# BluetoothModulePCBv1.net
KiCad netlist of a schematic drawn in EAGLE
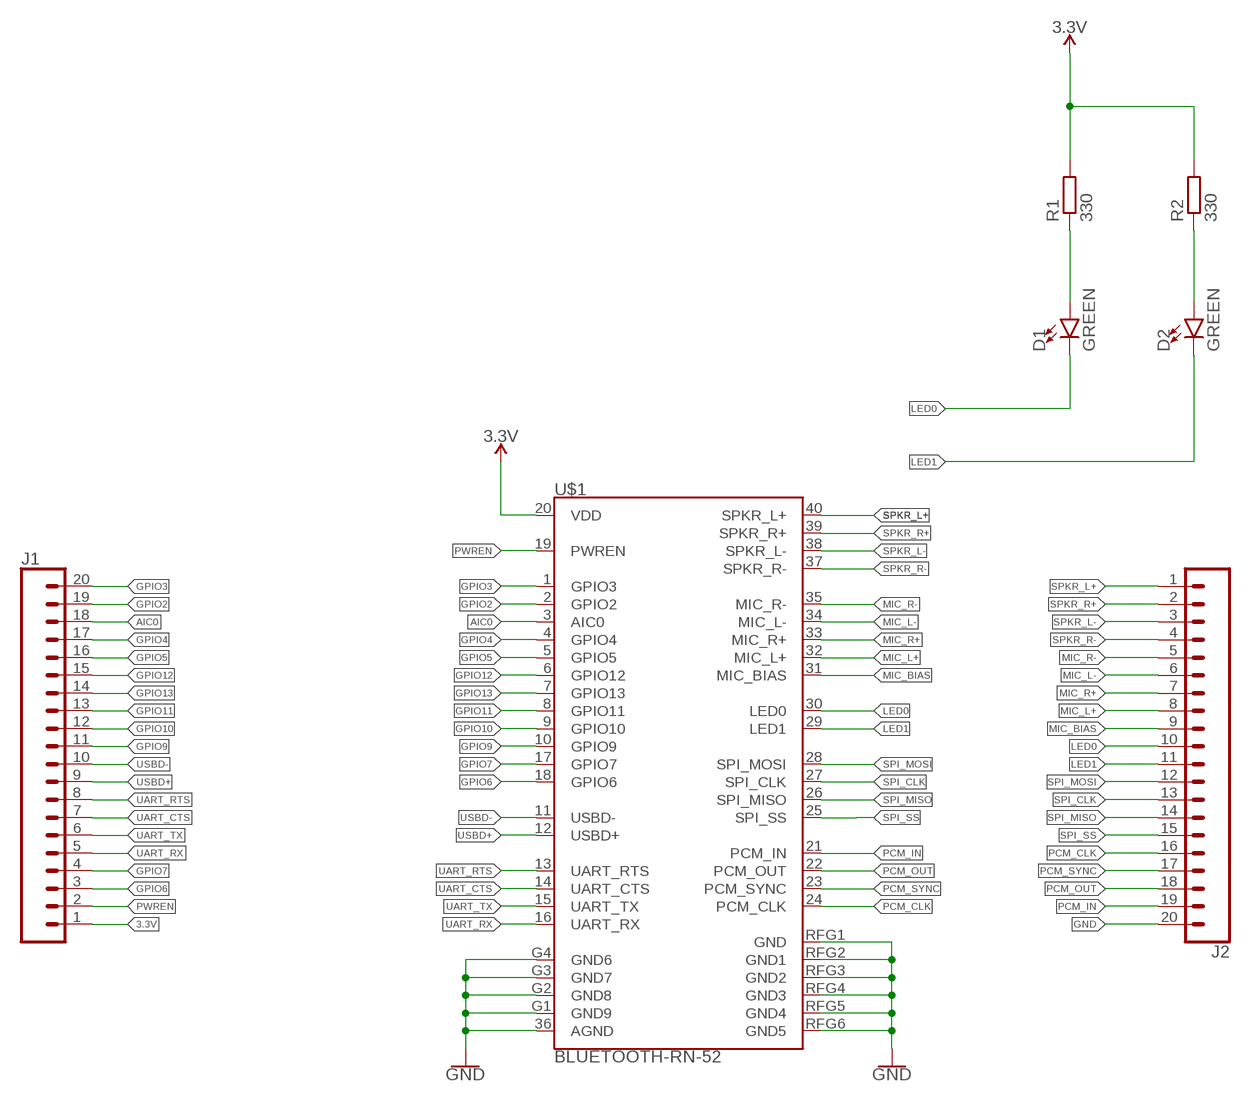
[diagram p0: schematic, sheet 1]

(export (version "E")
  (design (tool "Eeschema 10.0.6"))
  (components
    (comp (ref "D1")
      (value "GREEN")
      (footprint "eagle-import:LED_3MM")
      (libsource (lib "eagle-import") (part "LED3MM"))
    )
    (comp (ref "D2")
      (value "GREEN")
      (footprint "eagle-import:LED_3MM")
      (libsource (lib "eagle-import") (part "LED3MM"))
    )
    (comp (ref "J1")
      (value "CONN_20")
      (footprint "eagle-import:1X20")
      (libsource (lib "eagle-import") (part "CONN_20"))
    )
    (comp (ref "J2")
      (value "CONN_20")
      (footprint "eagle-import:1X20")
      (libsource (lib "eagle-import") (part "CONN_20"))
    )
    (comp (ref "R1")
      (value "330")
      (footprint "eagle-import:0204_7")
      (libsource (lib "eagle-import") (part "R-EU_0204/7"))
    )
    (comp (ref "R2")
      (value "330")
      (footprint "eagle-import:0204_7")
      (libsource (lib "eagle-import") (part "R-EU_0204/7"))
    )
    (comp (ref "U$1")
      (value "BLUETOOTH-RN-52")
      (footprint "eagle-import:RN-52")
      (libsource (lib "eagle-import") (part "BLUETOOTH-RN-52"))
    )
  )
  (nets
    (net (code "1") (name "3.3V") (class "Default")
      (node (ref "J1") (pin "1") (pinfunction "1_1") (pintype "passive"))
      (node (ref "R1") (pin "2") (pinfunction "2_2") (pintype "passive"))
      (node (ref "R2") (pin "2") (pinfunction "2_2") (pintype "passive"))
      (node (ref "U$1") (pin "20") (pinfunction "VDD_20") (pintype "bidirectional"))
    )
    (net (code "2") (name "AIC0") (class "Default")
      (node (ref "J1") (pin "18") (pinfunction "18_18") (pintype "passive"))
      (node (ref "U$1") (pin "3") (pinfunction "AIC0_3") (pintype "bidirectional"))
    )
    (net (code "3") (name "GND") (class "Default")
      (node (ref "J2") (pin "20") (pinfunction "20_20") (pintype "passive"))
      (node (ref "U$1") (pin "36") (pinfunction "AGND_36") (pintype "bidirectional"))
      (node (ref "U$1") (pin "G1") (pinfunction "GND9_G1") (pintype "bidirectional"))
      (node (ref "U$1") (pin "G2") (pinfunction "GND8_G2") (pintype "bidirectional"))
      (node (ref "U$1") (pin "G3") (pinfunction "GND7_G3") (pintype "bidirectional"))
      (node (ref "U$1") (pin "G4") (pinfunction "GND6_G4") (pintype "bidirectional"))
      (node (ref "U$1") (pin "RFG1") (pinfunction "GND_RFG1") (pintype "bidirectional"))
      (node (ref "U$1") (pin "RFG2") (pinfunction "GND1_RFG2") (pintype "bidirectional"))
      (node (ref "U$1") (pin "RFG3") (pinfunction "GND2_RFG3") (pintype "bidirectional"))
      (node (ref "U$1") (pin "RFG4") (pinfunction "GND3_RFG4") (pintype "bidirectional"))
      (node (ref "U$1") (pin "RFG5") (pinfunction "GND4_RFG5") (pintype "bidirectional"))
      (node (ref "U$1") (pin "RFG6") (pinfunction "GND5_RFG6") (pintype "bidirectional"))
    )
    (net (code "4") (name "GPIO2") (class "Default")
      (node (ref "J1") (pin "19") (pinfunction "19_19") (pintype "passive"))
      (node (ref "U$1") (pin "2") (pinfunction "GPIO2_2") (pintype "bidirectional"))
    )
    (net (code "5") (name "GPIO3") (class "Default")
      (node (ref "J1") (pin "20") (pinfunction "20_20") (pintype "passive"))
      (node (ref "U$1") (pin "1") (pinfunction "GPIO3_1") (pintype "bidirectional"))
    )
    (net (code "6") (name "GPIO4") (class "Default")
      (node (ref "J1") (pin "17") (pinfunction "17_17") (pintype "passive"))
      (node (ref "U$1") (pin "4") (pinfunction "GPIO4_4") (pintype "bidirectional"))
    )
    (net (code "7") (name "GPIO5") (class "Default")
      (node (ref "J1") (pin "16") (pinfunction "16_16") (pintype "passive"))
      (node (ref "U$1") (pin "5") (pinfunction "GPIO5_5") (pintype "bidirectional"))
    )
    (net (code "8") (name "GPIO6") (class "Default")
      (node (ref "J1") (pin "3") (pinfunction "3_3") (pintype "passive"))
      (node (ref "U$1") (pin "18") (pinfunction "GPIO6_18") (pintype "bidirectional"))
    )
    (net (code "9") (name "GPIO7") (class "Default")
      (node (ref "J1") (pin "4") (pinfunction "4_4") (pintype "passive"))
      (node (ref "U$1") (pin "17") (pinfunction "GPIO7_17") (pintype "bidirectional"))
    )
    (net (code "10") (name "GPIO9") (class "Default")
      (node (ref "J1") (pin "11") (pinfunction "11_11") (pintype "passive"))
      (node (ref "U$1") (pin "10") (pinfunction "GPIO9_10") (pintype "bidirectional"))
    )
    (net (code "11") (name "GPIO10") (class "Default")
      (node (ref "J1") (pin "12") (pinfunction "12_12") (pintype "passive"))
      (node (ref "U$1") (pin "9") (pinfunction "GPIO10_9") (pintype "bidirectional"))
    )
    (net (code "12") (name "GPIO11") (class "Default")
      (node (ref "J1") (pin "13") (pinfunction "13_13") (pintype "passive"))
      (node (ref "U$1") (pin "8") (pinfunction "GPIO11_8") (pintype "bidirectional"))
    )
    (net (code "13") (name "GPIO12") (class "Default")
      (node (ref "J1") (pin "15") (pinfunction "15_15") (pintype "passive"))
      (node (ref "U$1") (pin "6") (pinfunction "GPIO12_6") (pintype "bidirectional"))
    )
    (net (code "14") (name "GPIO13") (class "Default")
      (node (ref "J1") (pin "14") (pinfunction "14_14") (pintype "passive"))
      (node (ref "U$1") (pin "7") (pinfunction "GPIO13_7") (pintype "bidirectional"))
    )
    (net (code "15") (name "LED0") (class "Default")
      (node (ref "D1") (pin "K") (pinfunction "C_K") (pintype "passive"))
      (node (ref "J2") (pin "10") (pinfunction "10_10") (pintype "passive"))
      (node (ref "U$1") (pin "30") (pinfunction "LED0_30") (pintype "bidirectional"))
    )
    (net (code "16") (name "LED1") (class "Default")
      (node (ref "D2") (pin "K") (pinfunction "C_K") (pintype "passive"))
      (node (ref "J2") (pin "11") (pinfunction "11_11") (pintype "passive"))
      (node (ref "U$1") (pin "29") (pinfunction "LED1_29") (pintype "bidirectional"))
    )
    (net (code "17") (name "MIC_BIAS") (class "Default")
      (node (ref "J2") (pin "9") (pinfunction "9_9") (pintype "passive"))
      (node (ref "U$1") (pin "31") (pinfunction "MIC_BIAS_31") (pintype "bidirectional"))
    )
    (net (code "18") (name "MIC_L+") (class "Default")
      (node (ref "J2") (pin "8") (pinfunction "8_8") (pintype "passive"))
      (node (ref "U$1") (pin "32") (pinfunction "MIC_L+_32") (pintype "bidirectional"))
    )
    (net (code "19") (name "MIC_L-") (class "Default")
      (node (ref "J2") (pin "6") (pinfunction "6_6") (pintype "passive"))
      (node (ref "U$1") (pin "34") (pinfunction "MIC_L-_34") (pintype "bidirectional"))
    )
    (net (code "20") (name "MIC_R+") (class "Default")
      (node (ref "J2") (pin "7") (pinfunction "7_7") (pintype "passive"))
      (node (ref "U$1") (pin "33") (pinfunction "MIC_R+_33") (pintype "bidirectional"))
    )
    (net (code "21") (name "MIC_R-") (class "Default")
      (node (ref "J2") (pin "5") (pinfunction "5_5") (pintype "passive"))
      (node (ref "U$1") (pin "35") (pinfunction "MIC_R-_35") (pintype "bidirectional"))
    )
    (net (code "22") (name "Net-(D1-PadA)") (class "Default")
      (node (ref "D1") (pin "A") (pinfunction "A_A") (pintype "passive"))
      (node (ref "R1") (pin "1") (pinfunction "1_1") (pintype "passive"))
    )
    (net (code "23") (name "Net-(D2-PadA)") (class "Default")
      (node (ref "D2") (pin "A") (pinfunction "A_A") (pintype "passive"))
      (node (ref "R2") (pin "1") (pinfunction "1_1") (pintype "passive"))
    )
    (net (code "24") (name "PCM_CLK") (class "Default")
      (node (ref "J2") (pin "16") (pinfunction "16_16") (pintype "passive"))
      (node (ref "U$1") (pin "24") (pinfunction "PCM_CLK_24") (pintype "bidirectional"))
    )
    (net (code "25") (name "PCM_IN") (class "Default")
      (node (ref "J2") (pin "19") (pinfunction "19_19") (pintype "passive"))
      (node (ref "U$1") (pin "21") (pinfunction "PCM_IN_21") (pintype "bidirectional"))
    )
    (net (code "26") (name "PCM_OUT") (class "Default")
      (node (ref "J2") (pin "18") (pinfunction "18_18") (pintype "passive"))
      (node (ref "U$1") (pin "22") (pinfunction "PCM_OUT_22") (pintype "bidirectional"))
    )
    (net (code "27") (name "PCM_SYNC") (class "Default")
      (node (ref "J2") (pin "17") (pinfunction "17_17") (pintype "passive"))
      (node (ref "U$1") (pin "23") (pinfunction "PCM_SYNC_23") (pintype "bidirectional"))
    )
    (net (code "28") (name "PWREN") (class "Default")
      (node (ref "J1") (pin "2") (pinfunction "2_2") (pintype "passive"))
      (node (ref "U$1") (pin "19") (pinfunction "PWREN_19") (pintype "bidirectional"))
    )
    (net (code "29") (name "SPI_CLK") (class "Default")
      (node (ref "J2") (pin "13") (pinfunction "13_13") (pintype "passive"))
      (node (ref "U$1") (pin "27") (pinfunction "SPI_CLK_27") (pintype "bidirectional"))
    )
    (net (code "30") (name "SPI_MISO") (class "Default")
      (node (ref "J2") (pin "14") (pinfunction "14_14") (pintype "passive"))
      (node (ref "U$1") (pin "26") (pinfunction "SPI_MISO_26") (pintype "bidirectional"))
    )
    (net (code "31") (name "SPI_MOSI") (class "Default")
      (node (ref "J2") (pin "12") (pinfunction "12_12") (pintype "passive"))
      (node (ref "U$1") (pin "28") (pinfunction "SPI_MOSI_28") (pintype "bidirectional"))
    )
    (net (code "32") (name "SPI_SS") (class "Default")
      (node (ref "J2") (pin "15") (pinfunction "15_15") (pintype "passive"))
      (node (ref "U$1") (pin "25") (pinfunction "SPI_SS_25") (pintype "bidirectional"))
    )
    (net (code "33") (name "SPKR_L+") (class "Default")
      (node (ref "J2") (pin "1") (pinfunction "1_1") (pintype "passive"))
      (node (ref "U$1") (pin "40") (pinfunction "SPKR_L+_40") (pintype "bidirectional"))
    )
    (net (code "34") (name "SPKR_L-") (class "Default")
      (node (ref "J2") (pin "3") (pinfunction "3_3") (pintype "passive"))
      (node (ref "U$1") (pin "38") (pinfunction "SPKR_L-_38") (pintype "bidirectional"))
    )
    (net (code "35") (name "SPKR_R+") (class "Default")
      (node (ref "J2") (pin "2") (pinfunction "2_2") (pintype "passive"))
      (node (ref "U$1") (pin "39") (pinfunction "SPKR_R+_39") (pintype "bidirectional"))
    )
    (net (code "36") (name "SPKR_R-") (class "Default")
      (node (ref "J2") (pin "4") (pinfunction "4_4") (pintype "passive"))
      (node (ref "U$1") (pin "37") (pinfunction "SPKR_R-_37") (pintype "bidirectional"))
    )
    (net (code "37") (name "UART_CTS") (class "Default")
      (node (ref "J1") (pin "7") (pinfunction "7_7") (pintype "passive"))
      (node (ref "U$1") (pin "14") (pinfunction "UART_CTS_14") (pintype "bidirectional"))
    )
    (net (code "38") (name "UART_RTS") (class "Default")
      (node (ref "J1") (pin "8") (pinfunction "8_8") (pintype "passive"))
      (node (ref "U$1") (pin "13") (pinfunction "UART_RTS_13") (pintype "bidirectional"))
    )
    (net (code "39") (name "UART_RX") (class "Default")
      (node (ref "J1") (pin "5") (pinfunction "5_5") (pintype "passive"))
      (node (ref "U$1") (pin "16") (pinfunction "UART_RX_16") (pintype "bidirectional"))
    )
    (net (code "40") (name "UART_TX") (class "Default")
      (node (ref "J1") (pin "6") (pinfunction "6_6") (pintype "passive"))
      (node (ref "U$1") (pin "15") (pinfunction "UART_TX_15") (pintype "bidirectional"))
    )
    (net (code "41") (name "USBD+") (class "Default")
      (node (ref "J1") (pin "9") (pinfunction "9_9") (pintype "passive"))
      (node (ref "U$1") (pin "12") (pinfunction "USBD+_12") (pintype "bidirectional"))
    )
    (net (code "42") (name "USBD-") (class "Default")
      (node (ref "J1") (pin "10") (pinfunction "10_10") (pintype "passive"))
      (node (ref "U$1") (pin "11") (pinfunction "USBD-_11") (pintype "bidirectional"))
    )
  )
)
